# design.net
KiCad netlist of a schematic drawn in EAGLE
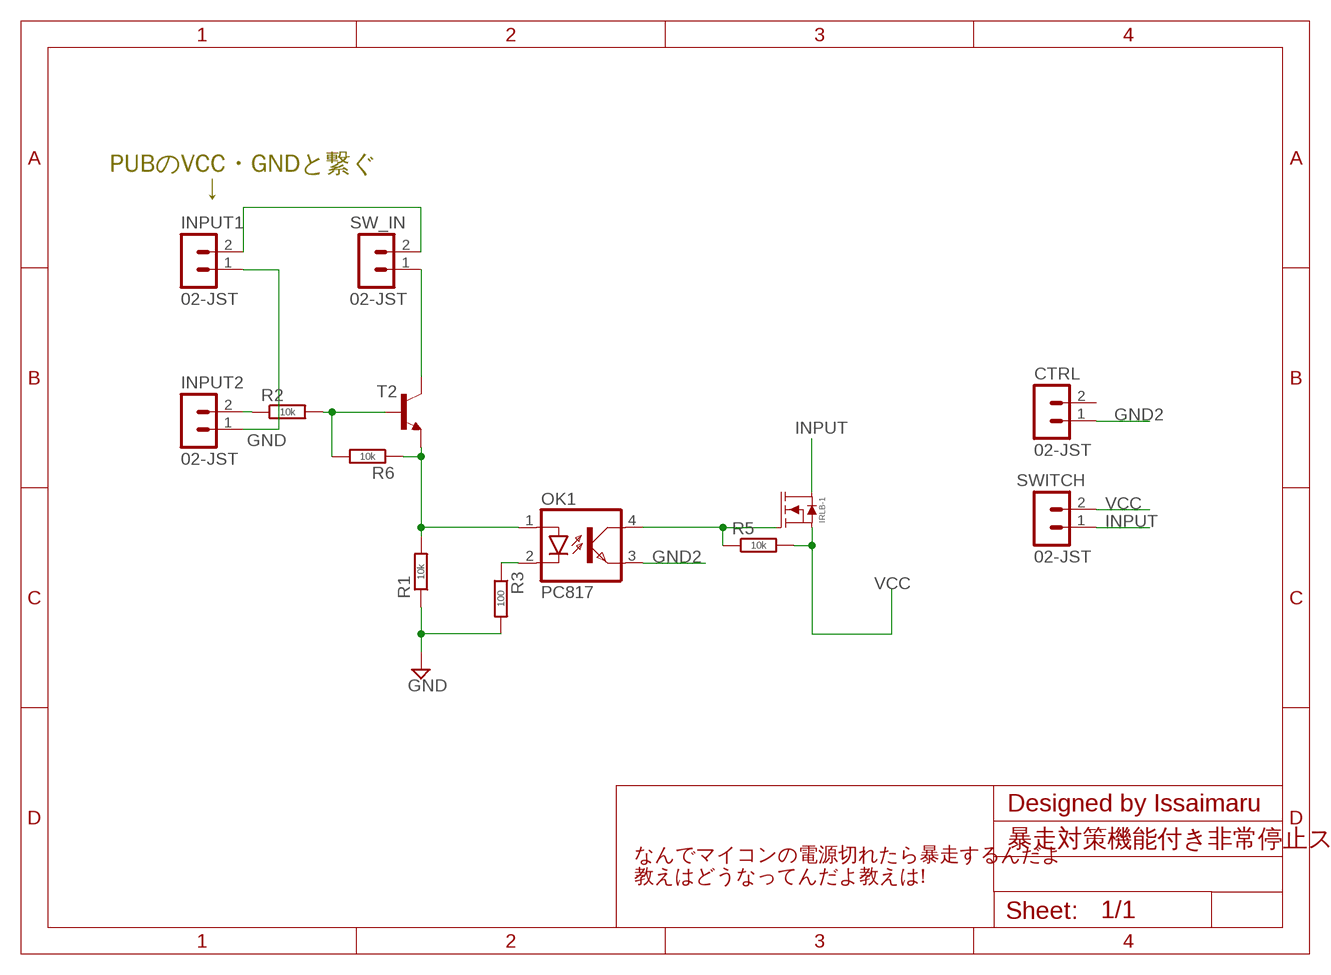
[diagram p0: schematic, sheet 1]

(export (version "E")
  (design (tool "Eeschema 10.0.6"))
  (components
    (comp (ref "CTRL")
      (value "02-JST")
      (footprint "eagle-import:B2B-XH")
      (libsource (lib "eagle-import") (part "02-JST"))
    )
    (comp (ref "INPUT1")
      (value "02-JST")
      (footprint "eagle-import:B2B-XH")
      (libsource (lib "eagle-import") (part "02-JST"))
    )
    (comp (ref "INPUT2")
      (value "02-JST")
      (footprint "eagle-import:B2B-XH")
      (libsource (lib "eagle-import") (part "02-JST"))
    )
    (comp (ref "IRLB-1")
      (value "IRLB3813STAND")
      (footprint "eagle-import:TO-220AB-STAND")
      (libsource (lib "eagle-import") (part "IRLB3813STAND"))
    )
    (comp (ref "OK1")
      (value "PC817")
      (footprint "eagle-import:DIL04")
      (fields (field (name "MPN") "PC817X4J000F"))
      (libsource (lib "eagle-import") (part "PC817"))
    )
    (comp (ref "R1")
      (value "10k")
      (footprint "eagle-import:0204_7")
      (libsource (lib "eagle-import") (part "R-EU_0204/7"))
    )
    (comp (ref "R2")
      (value "10k")
      (footprint "eagle-import:0204_7")
      (libsource (lib "eagle-import") (part "R-EU_0204/7"))
    )
    (comp (ref "R3")
      (value "100")
      (footprint "eagle-import:0204_7")
      (libsource (lib "eagle-import") (part "R-EU_0204/7"))
    )
    (comp (ref "R5")
      (value "10k")
      (footprint "eagle-import:0204_7")
      (libsource (lib "eagle-import") (part "R-EU_0204/7"))
    )
    (comp (ref "R6")
      (value "10k")
      (footprint "eagle-import:0204_7")
      (libsource (lib "eagle-import") (part "R-EU_0204/7"))
    )
    (comp (ref "SWITCH")
      (value "02-JST")
      (footprint "eagle-import:B2B-XH")
      (libsource (lib "eagle-import") (part "02-JST"))
    )
    (comp (ref "SW_IN")
      (value "02-JST")
      (footprint "eagle-import:B2B-XH")
      (libsource (lib "eagle-import") (part "02-JST"))
    )
    (comp (ref "T2")
      (value "一般的なトランジスタ")
      (footprint "eagle-import:TO92-CEB")
      (libsource (lib "eagle-import") (part "一般的なトランジスタ"))
    )
  )
  (nets
    (net (code "1") (name "/GND2") (class "Default")
      (node (ref "CTRL") (pin "1") (pinfunction "1_1") (pintype "passive"))
      (node (ref "OK1") (pin "3") (pinfunction "EMIT_3") (pintype "passive"))
    )
    (net (code "2") (name "/INPUT") (class "Default")
      (node (ref "IRLB-1") (pin "D") (pinfunction "D_D") (pintype "passive"))
      (node (ref "SWITCH") (pin "1") (pinfunction "1_1") (pintype "passive"))
    )
    (net (code "3") (name "/VCC") (class "Default")
      (node (ref "IRLB-1") (pin "S") (pinfunction "S_S") (pintype "passive"))
      (node (ref "R5") (pin "2") (pinfunction "2_2") (pintype "passive"))
      (node (ref "SWITCH") (pin "2") (pinfunction "2_2") (pintype "passive"))
    )
    (net (code "4") (name "GND") (class "Default")
      (node (ref "INPUT1") (pin "1") (pinfunction "1_1") (pintype "passive"))
      (node (ref "INPUT2") (pin "1") (pinfunction "1_1") (pintype "passive"))
      (node (ref "R1") (pin "1") (pinfunction "1_1") (pintype "passive"))
      (node (ref "R3") (pin "2") (pinfunction "2_2") (pintype "passive"))
    )
    (net (code "5") (name "Net-(INPUT1-Pad2)") (class "Default")
      (node (ref "INPUT1") (pin "2") (pinfunction "2_2") (pintype "passive"))
      (node (ref "SW_IN") (pin "2") (pinfunction "2_2") (pintype "passive"))
    )
    (net (code "6") (name "Net-(INPUT2-Pad2)") (class "Default")
      (node (ref "INPUT2") (pin "2") (pinfunction "2_2") (pintype "passive"))
      (node (ref "R2") (pin "1") (pinfunction "1_1") (pintype "passive"))
    )
    (net (code "7") (name "Net-(OK1-A)") (class "Default")
      (node (ref "OK1") (pin "1") (pinfunction "A_1") (pintype "passive"))
      (node (ref "R1") (pin "2") (pinfunction "2_2") (pintype "passive"))
      (node (ref "R6") (pin "1") (pinfunction "1_1") (pintype "passive"))
      (node (ref "T2") (pin "E") (pinfunction "E_E") (pintype "passive"))
    )
    (net (code "8") (name "Net-(OK1-C)") (class "Default")
      (node (ref "OK1") (pin "2") (pinfunction "C_2") (pintype "passive"))
      (node (ref "R3") (pin "1") (pinfunction "1_1") (pintype "passive"))
    )
    (net (code "9") (name "Net-(OK1-COL)") (class "Default")
      (node (ref "IRLB-1") (pin "G") (pinfunction "G_G") (pintype "passive"))
      (node (ref "OK1") (pin "4") (pinfunction "COL_4") (pintype "passive"))
      (node (ref "R5") (pin "1") (pinfunction "1_1") (pintype "passive"))
    )
    (net (code "10") (name "Net-(R2-Pad2)") (class "Default")
      (node (ref "R2") (pin "2") (pinfunction "2_2") (pintype "passive"))
      (node (ref "R6") (pin "2") (pinfunction "2_2") (pintype "passive"))
      (node (ref "T2") (pin "B") (pinfunction "B_B") (pintype "passive"))
    )
    (net (code "11") (name "Net-(SW_IN-Pad1)") (class "Default")
      (node (ref "SW_IN") (pin "1") (pinfunction "1_1") (pintype "passive"))
      (node (ref "T2") (pin "C") (pinfunction "C_C") (pintype "passive"))
    )
    (net (code "12") (name "unconnected-(CTRL-Pad2)") (class "Default")
      (node (ref "CTRL") (pin "2") (pinfunction "2_2") (pintype "passive"))
    )
  )
)
